# CAN_RS232.net
KiCad netlist of a schematic drawn in Altium Designer
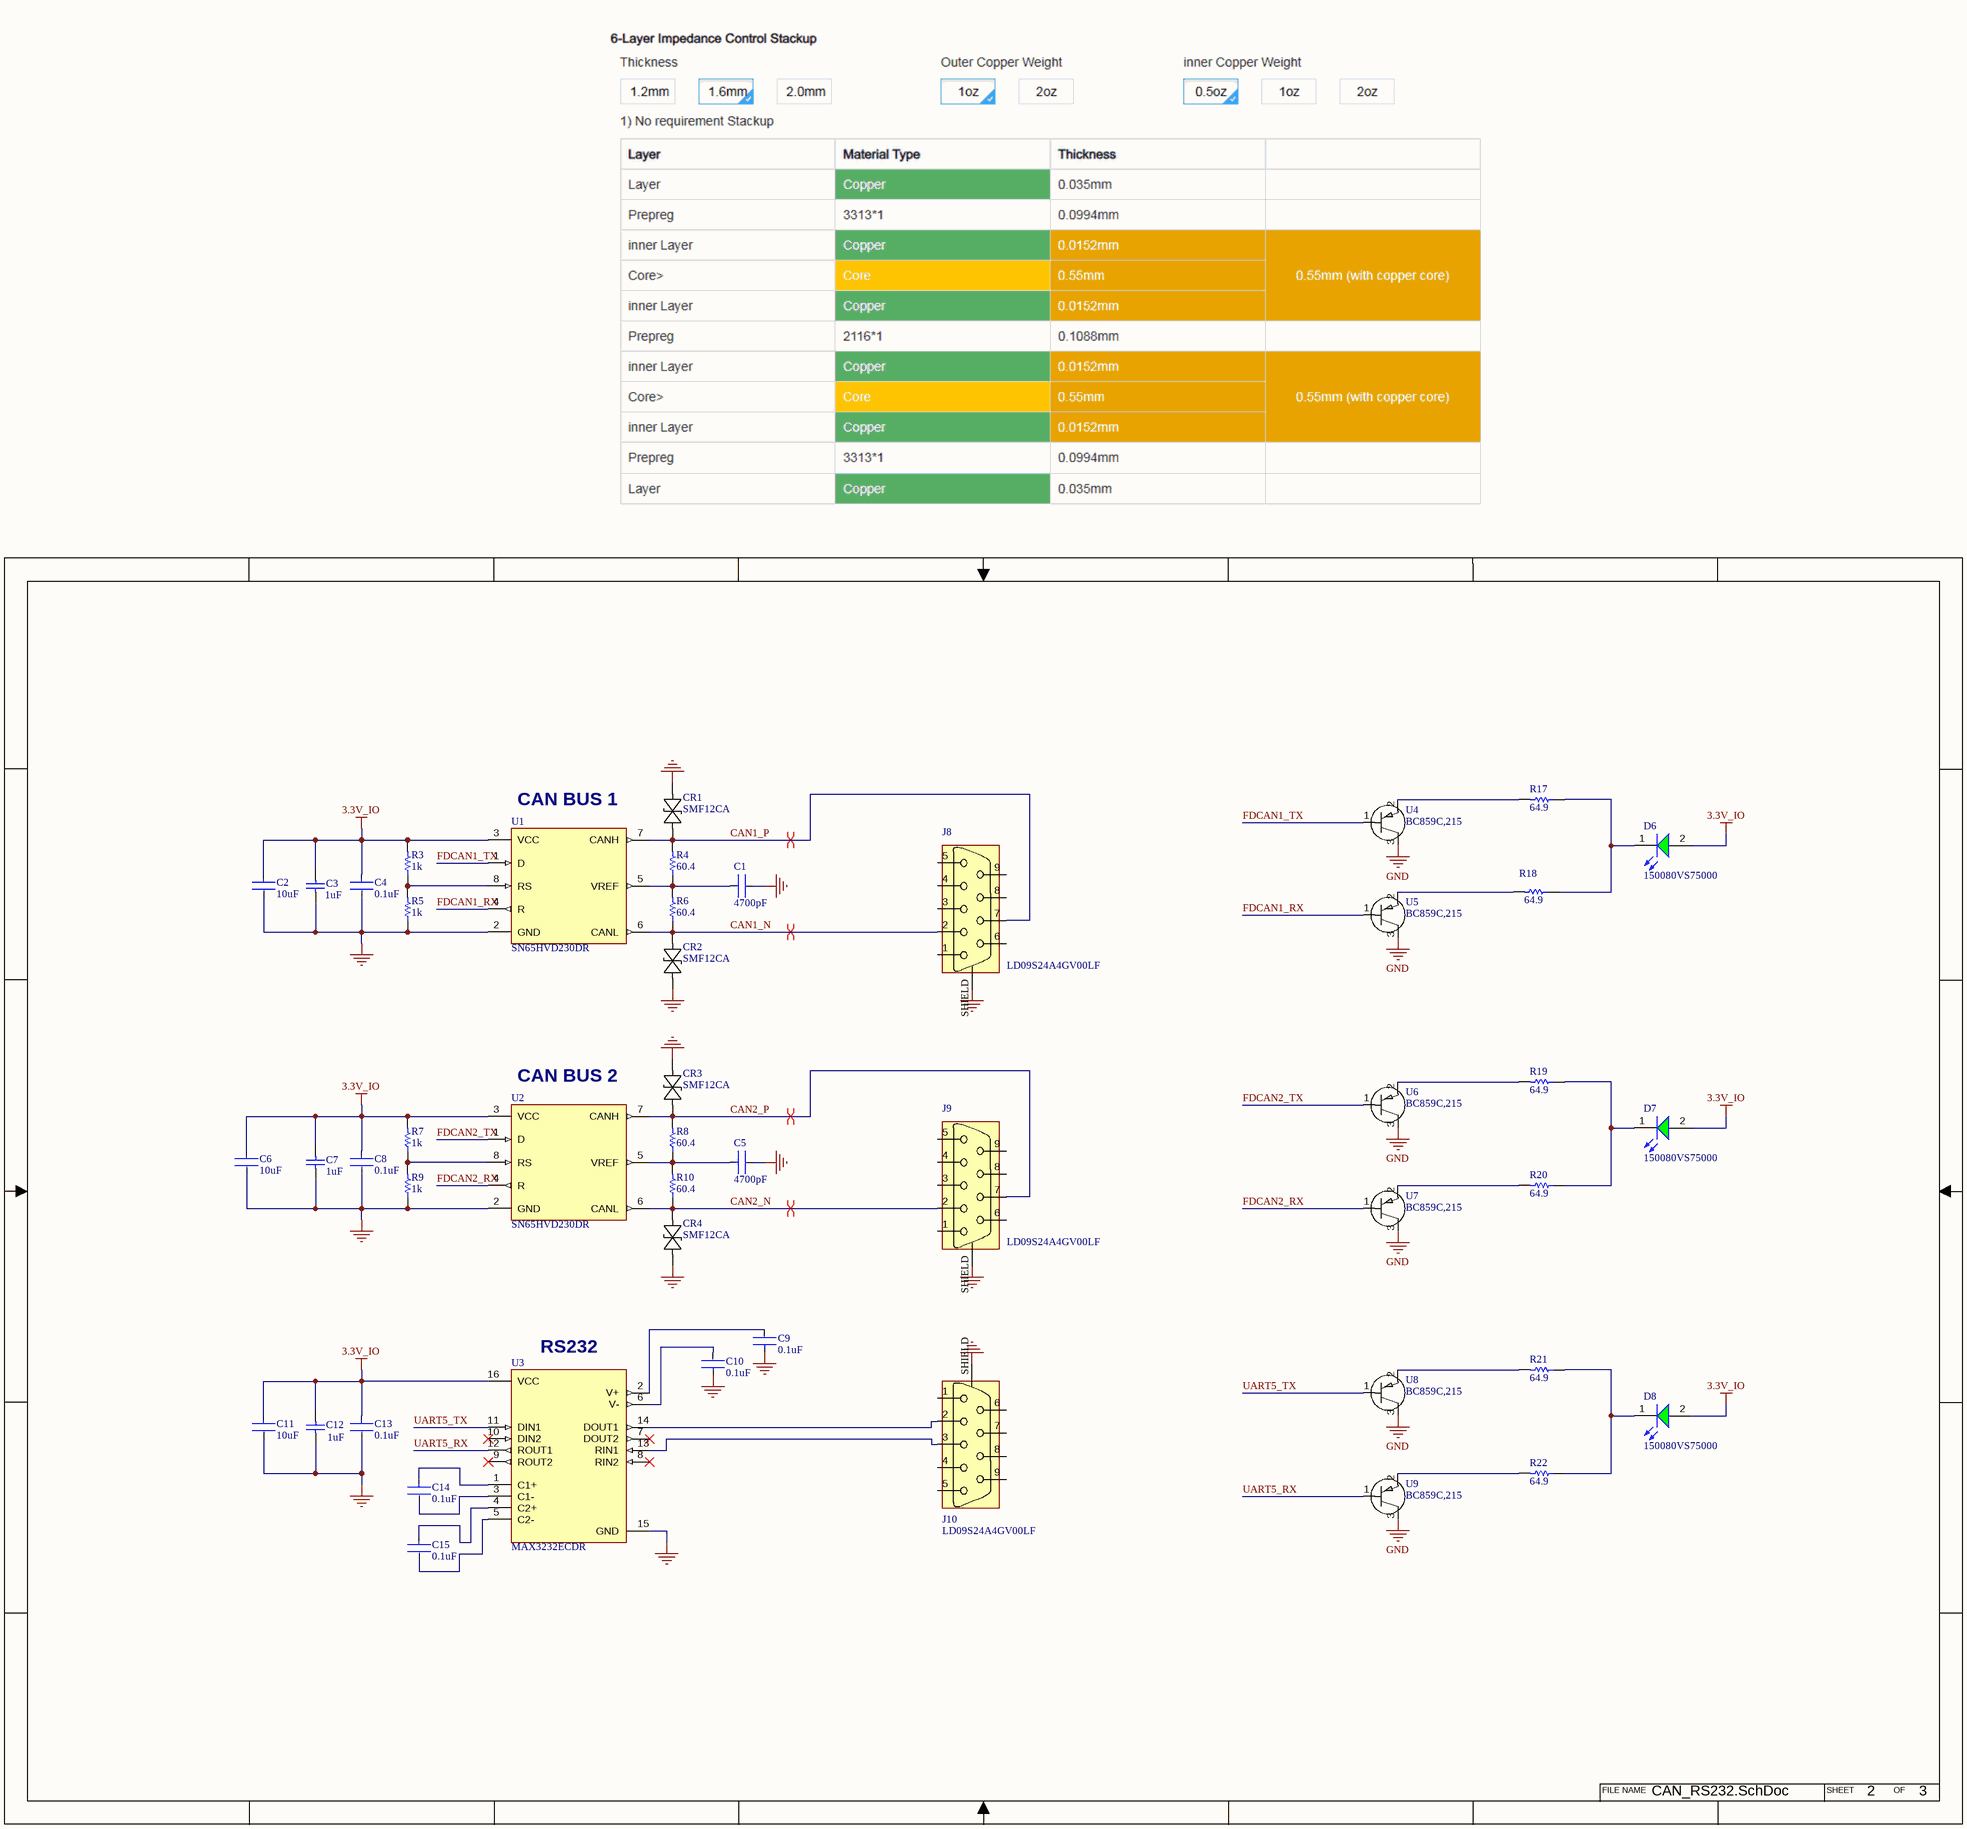
[diagram p0: CAN_RS232.SchDoc]

(export (version "E")
  (design (tool "Eeschema 10.0.6"))
  (components
    (comp (ref "C1")
      (value "4700pF")
      (footprint "FP-CC0805-0_85-MFG")
      (description "CAP CER 4700PF 50V X7R 0805")
      (fields (field (name "TOLERANCE") "0.1") (field (name "MANUFACTURER") "Yageo"))
      (libsource (lib "Altium Content Vault") (part "11868f565c42a9108669ba33697ecf6"))
    )
    (comp (ref "C2")
      (value "10uF")
      (footprint "FP-CL31-IPC_B")
      (description "Cap Ceramic 10uF 25V X7R ±10% SMD 1206 +125°C Embossed T/R")
      (fields (field (name "TOLERANCE") "10%"))
      (libsource (lib "Altium Content Vault") (part "b4654b650e69147ec39a6b967a45e02"))
    )
    (comp (ref "C3")
      (value "1uF")
      (footprint "CAPC2013X100X50ML20T25")
      (description "C0805C105K8RACTU")
      (fields (field (name "MANUFACTURER") "Kemet"))
      (libsource (lib "Altium Content Vault") (part "CAP"))
    )
    (comp (ref "C4")
      (value "0.1uF")
      (footprint "FP-CC0805-0_85-MFG")
      (description "CAP CER 0.1UF 50V X7R 0805")
      (fields (field (name "TOLERANCE") "0.1") (field (name "MANUFACTURER PART NUMBER") "CC0805KRX7R9BB104"))
      (libsource (lib "Altium Content Vault") (part "11868f565c42a9108669ba33697ecf6"))
    )
    (comp (ref "C5")
      (value "4700pF")
      (footprint "FP-CC0805-0_85-MFG")
      (description "CAP CER 4700PF 50V X7R 0805")
      (fields (field (name "TOLERANCE") "0.1") (field (name "MANUFACTURER") "Yageo"))
      (libsource (lib "Altium Content Vault") (part "11868f565c42a9108669ba33697ecf6"))
    )
    (comp (ref "C6")
      (value "10uF")
      (footprint "FP-CL31-IPC_B")
      (description "Cap Ceramic 10uF 25V X7R ±10% SMD 1206 +125°C Embossed T/R")
      (fields (field (name "TOLERANCE") "10%"))
      (libsource (lib "Altium Content Vault") (part "b4654b650e69147ec39a6b967a45e02"))
    )
    (comp (ref "C7")
      (value "1uF")
      (footprint "CAPC2013X100X50ML20T25")
      (fields (field (name "PART NUMBER") "C0805C105K8RACTU") (field (name "MANUFACTURER") "Kemet"))
      (libsource (lib "Altium Content Vault") (part "CAP"))
    )
    (comp (ref "C8")
      (value "0.1uF")
      (footprint "FP-CC0805-0_85-MFG")
      (description "CAP CER 0.1UF 50V X7R 0805")
      (fields (field (name "TOLERANCE") "0.1") (field (name "MANUFACTURER PART NUMBER") "CC0805KRX7R9BB104"))
      (libsource (lib "Altium Content Vault") (part "11868f565c42a9108669ba33697ecf6"))
    )
    (comp (ref "C9")
      (value "0.1uF")
      (footprint "FP-CC0805-0_85-MFG")
      (description "CAP CER 0.1UF 50V X7R 0805")
      (fields (field (name "TOLERANCE") "0.1") (field (name "MANUFACTURER PART NUMBER") "CC0805KRX7R9BB104"))
      (libsource (lib "Altium Content Vault") (part "11868f565c42a9108669ba33697ecf6"))
    )
    (comp (ref "C10")
      (value "0.1uF")
      (footprint "FP-CC0805-0_85-MFG")
      (description "CAP CER 0.1UF 50V X7R 0805")
      (fields (field (name "TOLERANCE") "0.1") (field (name "MANUFACTURER PART NUMBER") "CC0805KRX7R9BB104"))
      (libsource (lib "Altium Content Vault") (part "11868f565c42a9108669ba33697ecf6"))
    )
    (comp (ref "C11")
      (value "10uF")
      (footprint "FP-CL31-IPC_B")
      (description "Cap Ceramic 10uF 25V X7R ±10% SMD 1206 +125°C Embossed T/R")
      (fields (field (name "TOLERANCE") "10%"))
      (libsource (lib "Altium Content Vault") (part "b4654b650e69147ec39a6b967a45e02"))
    )
    (comp (ref "C12")
      (value "1uF")
      (footprint "CAPC2013X100X50ML20T25")
      (fields (field (name "PART NUMBER") "C0805C105K8RACTU") (field (name "MANUFACTURER") "Kemet"))
      (libsource (lib "Altium Content Vault") (part "CAP"))
    )
    (comp (ref "C13")
      (value "0.1uF")
      (footprint "FP-CC0805-0_85-MFG")
      (description "CAP CER 0.1UF 50V X7R 0805")
      (fields (field (name "TOLERANCE") "0.1") (field (name "MANUFACTURER PART NUMBER") "CC0805KRX7R9BB104"))
      (libsource (lib "Altium Content Vault") (part "11868f565c42a9108669ba33697ecf6"))
    )
    (comp (ref "C14")
      (value "0.1uF")
      (footprint "FP-CC0805-0_85-MFG")
      (description "CAP CER 0.1UF 50V X7R 0805")
      (fields (field (name "TOLERANCE") "0.1") (field (name "MANUFACTURER PART NUMBER") "CC0805KRX7R9BB104"))
      (libsource (lib "Altium Content Vault") (part "11868f565c42a9108669ba33697ecf6"))
    )
    (comp (ref "C15")
      (value "0.1uF")
      (footprint "FP-CC0805-0_85-MFG")
      (description "CAP CER 0.1UF 50V X7R 0805")
      (fields (field (name "TOLERANCE") "0.1") (field (name "MANUFACTURER PART NUMBER") "CC0805KRX7R9BB104"))
      (libsource (lib "Altium Content Vault") (part "11868f565c42a9108669ba33697ecf6"))
    )
    (comp (ref "CR1")
      (value "SMF12CA")
      (footprint "SOD-123F_LTF")
      (description "No Description Available")
      (libsource (lib "SMF12CA") (part "SMF12CA"))
    )
    (comp (ref "CR2")
      (value "SMF12CA")
      (footprint "SOD-123F_LTF")
      (description "No Description Available")
      (libsource (lib "SMF12CA") (part "SMF12CA"))
    )
    (comp (ref "CR3")
      (value "SMF12CA")
      (footprint "SOD-123F_LTF")
      (description "No Description Available")
      (libsource (lib "SMF12CA") (part "SMF12CA"))
    )
    (comp (ref "CR4")
      (value "SMF12CA")
      (footprint "SOD-123F_LTF")
      (description "No Description Available")
      (libsource (lib "SMF12CA") (part "SMF12CA"))
    )
    (comp (ref "D6")
      (value "150080VS75000")
      (footprint "WL-SMCW_0805_150080xx75000")
      (description "WL-SMCW SMT Mono-Color Chip LED Waterclear")
      (libsource (lib "Altium Content Vault") (part "LED_Green_2A-1K"))
    )
    (comp (ref "D7")
      (value "150080VS75000")
      (footprint "WL-SMCW_0805_150080xx75000")
      (description "WL-SMCW SMT Mono-Color Chip LED Waterclear")
      (libsource (lib "Altium Content Vault") (part "LED_Green_2A-1K"))
    )
    (comp (ref "D8")
      (value "150080VS75000")
      (footprint "WL-SMCW_0805_150080xx75000")
      (description "WL-SMCW SMT Mono-Color Chip LED Waterclear")
      (libsource (lib "Altium Content Vault") (part "LED_Green_2A-1K"))
    )
    (comp (ref "J8")
      (value "LD09S24A4GV00LF")
      (footprint "ASSMANN_A-DF09A/KG-T2S")
      (description "No Description Available")
      (libsource (lib "LD09S24A4GV00LF") (part "LD09S24A4GV00LF"))
    )
    (comp (ref "J9")
      (value "LD09S24A4GV00LF")
      (footprint "ASSMANN_A-DF09A/KG-T2S")
      (description "No Description Available")
      (libsource (lib "LD09S24A4GV00LF") (part "LD09S24A4GV00LF"))
    )
    (comp (ref "J10")
      (value "LD09S24A4GV00LF")
      (footprint "ASSMANN_A-DF09A/KG-T2S")
      (description "No Description Available")
      (libsource (lib "") (part "LD09S24A4GV00LF_1"))
    )
    (comp (ref "R3")
      (value "1k")
      (footprint "RESC2013X60X35ML10T20")
      (description "Chip Resistor, 1 KOhm, +/- 1%, 125 mW, -55 to 155 degC, 0805 (2012 Metric), RoHS, Tape and Reel")
      (fields (field (name "TOLERANCE") "1%") (field (name "MANUFACTURER") "Yageo"))
      (libsource (lib "Altium Content Vault") (part "RES-2"))
    )
    (comp (ref "R4")
      (value "60.4")
      (footprint "RESC2013X60X35LL10T20")
      (fields (field (name "PART NUMBER") "RC0805FR-0760R4L") (field (name "MANUFACTURER") "Yageo"))
      (libsource (lib "Altium Content Vault") (part "RES"))
    )
    (comp (ref "R5")
      (value "1k")
      (footprint "RESC2013X60X35ML10T20")
      (description "Chip Resistor, 1 KOhm, +/- 1%, 125 mW, -55 to 155 degC, 0805 (2012 Metric), RoHS, Tape and Reel")
      (fields (field (name "TOLERANCE") "1%") (field (name "MANUFACTURER") "Yageo"))
      (libsource (lib "Altium Content Vault") (part "RES-2"))
    )
    (comp (ref "R6")
      (value "60.4")
      (footprint "RESC2013X60X35LL10T20")
      (fields (field (name "PART NUMBER") "RC0805FR-0760R4L") (field (name "MANUFACTURER") "Yageo"))
      (libsource (lib "Altium Content Vault") (part "RES"))
    )
    (comp (ref "R7")
      (value "1k")
      (footprint "RESC2013X60X35ML10T20")
      (description "Chip Resistor, 1 KOhm, +/- 1%, 125 mW, -55 to 155 degC, 0805 (2012 Metric), RoHS, Tape and Reel")
      (fields (field (name "TOLERANCE") "1%") (field (name "MANUFACTURER") "Yageo"))
      (libsource (lib "Altium Content Vault") (part "RES-2"))
    )
    (comp (ref "R8")
      (value "60.4")
      (footprint "RESC2013X60X35LL10T20")
      (fields (field (name "PART NUMBER") "RC0805FR-0760R4L") (field (name "MANUFACTURER") "Yageo"))
      (libsource (lib "Altium Content Vault") (part "RES"))
    )
    (comp (ref "R9")
      (value "1k")
      (footprint "RESC2013X60X35ML10T20")
      (description "Chip Resistor, 1 KOhm, +/- 1%, 125 mW, -55 to 155 degC, 0805 (2012 Metric), RoHS, Tape and Reel")
      (fields (field (name "TOLERANCE") "1%") (field (name "MANUFACTURER") "Yageo"))
      (libsource (lib "Altium Content Vault") (part "RES-2"))
    )
    (comp (ref "R10")
      (value "60.4")
      (footprint "RESC2013X60X35LL10T20")
      (fields (field (name "PART NUMBER") "RC0805FR-0760R4L") (field (name "MANUFACTURER") "Yageo"))
      (libsource (lib "Altium Content Vault") (part "RES"))
    )
    (comp (ref "R17")
      (value "64.9")
      (footprint "RESC2013X60X35LL10T20")
      (fields (field (name "PART NUMBER") "RC0805FR-0764R9L") (field (name "MANUFACTURER") "Yageo"))
      (libsource (lib "Altium Content Vault") (part "RES"))
    )
    (comp (ref "R18")
      (value "64.9")
      (footprint "RESC2013X60X35LL10T20")
      (fields (field (name "PART NUMBER") "RC0805FR-0764R9L") (field (name "MANUFACTURER") "Yageo"))
      (libsource (lib "Altium Content Vault") (part "RES"))
    )
    (comp (ref "R19")
      (value "64.9")
      (footprint "RESC2013X60X35LL10T20")
      (fields (field (name "PART NUMBER") "RC0805FR-0764R9L") (field (name "MANUFACTURER") "Yageo"))
      (libsource (lib "Altium Content Vault") (part "RES"))
    )
    (comp (ref "R20")
      (value "64.9")
      (footprint "RESC2013X60X35LL10T20")
      (fields (field (name "PART NUMBER") "RC0805FR-0764R9L") (field (name "MANUFACTURER") "Yageo"))
      (libsource (lib "Altium Content Vault") (part "RES"))
    )
    (comp (ref "R21")
      (value "64.9")
      (footprint "RESC2013X60X35LL10T20")
      (fields (field (name "PART NUMBER") "RC0805FR-0764R9L") (field (name "MANUFACTURER") "Yageo"))
      (libsource (lib "Altium Content Vault") (part "RES"))
    )
    (comp (ref "R22")
      (value "64.9")
      (footprint "RESC2013X60X35LL10T20")
      (fields (field (name "PART NUMBER") "RC0805FR-0764R9L") (field (name "MANUFACTURER") "Yageo"))
      (libsource (lib "Altium Content Vault") (part "RES"))
    )
    (comp (ref "U1")
      (value "SN65HVD230DR")
      (footprint "SOIC127P599X175-8N")
      (description "3.3 V CAN Transceiver with Standby Mode 8-SOIC -40 to 85")
      (fields (field (name "MF") "Texas Instruments"))
      (libsource (lib "ertc_symbols") (part "SN65HVD230DR"))
    )
    (comp (ref "U2")
      (value "SN65HVD230DR")
      (footprint "SOIC127P599X175-8N")
      (description "3.3 V CAN Transceiver with Standby Mode 8-SOIC -40 to 85")
      (fields (field (name "MF") "Texas Instruments"))
      (libsource (lib "ertc_symbols") (part "SN65HVD230DR"))
    )
    (comp (ref "U3")
      (value "MAX3232ECDR")
      (footprint "SOIC127P600X175-16N:SOIC127P600X175-16N")
      (libsource (lib "MAX3232ECDR") (part "MAX3232ECDR"))
    )
    (comp (ref "U4")
      (value "BC859C,215")
      (footprint "SOT23_NEX")
      (description "No Description Available")
      (libsource (lib "BC859C,215") (part "BC859C,215"))
    )
    (comp (ref "U5")
      (value "BC859C,215")
      (footprint "SOT23_NEX")
      (description "No Description Available")
      (libsource (lib "BC859C,215") (part "BC859C,215"))
    )
    (comp (ref "U6")
      (value "BC859C,215")
      (footprint "SOT23_NEX")
      (description "No Description Available")
      (libsource (lib "BC859C,215") (part "BC859C,215"))
    )
    (comp (ref "U7")
      (value "BC859C,215")
      (footprint "SOT23_NEX")
      (description "No Description Available")
      (libsource (lib "BC859C,215") (part "BC859C,215"))
    )
    (comp (ref "U8")
      (value "BC859C,215")
      (footprint "SOT23_NEX")
      (description "No Description Available")
      (libsource (lib "BC859C,215") (part "BC859C,215"))
    )
    (comp (ref "U9")
      (value "BC859C,215")
      (footprint "SOT23_NEX")
      (description "No Description Available")
      (libsource (lib "BC859C,215") (part "BC859C,215"))
    )
  )
  (nets
    (net (code "1") (name "/CAN1_N") (class "Default")
      (node (ref "CR2") (pin "2") (pinfunction "2_2") (pintype "passive"))
      (node (ref "J8") (pin "2") (pinfunction "2_2") (pintype "passive"))
      (node (ref "R6") (pin "1") (pinfunction "1_1") (pintype "passive"))
      (node (ref "U1") (pin "6") (pinfunction "CANL_6") (pintype "output"))
    )
    (net (code "2") (name "/CAN1_P") (class "Default")
      (node (ref "CR1") (pin "2") (pinfunction "2_2") (pintype "passive"))
      (node (ref "J8") (pin "7") (pinfunction "7_7") (pintype "passive"))
      (node (ref "R4") (pin "2") (pinfunction "2_2") (pintype "passive"))
      (node (ref "U1") (pin "7") (pinfunction "CANH_7") (pintype "output"))
    )
    (net (code "3") (name "/CAN2_N") (class "Default")
      (node (ref "CR4") (pin "1") (pinfunction "1_1") (pintype "passive"))
      (node (ref "J9") (pin "2") (pinfunction "2_2") (pintype "passive"))
      (node (ref "R10") (pin "1") (pinfunction "1_1") (pintype "passive"))
      (node (ref "U2") (pin "6") (pinfunction "CANL_6") (pintype "output"))
    )
    (net (code "4") (name "/CAN2_P") (class "Default")
      (node (ref "CR3") (pin "1") (pinfunction "1_1") (pintype "passive"))
      (node (ref "J9") (pin "7") (pinfunction "7_7") (pintype "passive"))
      (node (ref "R8") (pin "2") (pinfunction "2_2") (pintype "passive"))
      (node (ref "U2") (pin "7") (pinfunction "CANH_7") (pintype "output"))
    )
    (net (code "5") (name "/FDCAN1_RX") (class "Default")
      (node (ref "U1") (pin "4") (pinfunction "R_4") (pintype "output"))
      (node (ref "U5") (pin "1") (pinfunction "Base_1") (pintype "passive"))
    )
    (net (code "6") (name "/FDCAN1_TX") (class "Default")
      (node (ref "U1") (pin "1") (pinfunction "D_1") (pintype "input"))
      (node (ref "U4") (pin "1") (pinfunction "Base_1") (pintype "passive"))
    )
    (net (code "7") (name "/FDCAN2_RX") (class "Default")
      (node (ref "U2") (pin "4") (pinfunction "R_4") (pintype "output"))
      (node (ref "U7") (pin "1") (pinfunction "Base_1") (pintype "passive"))
    )
    (net (code "8") (name "/FDCAN2_TX") (class "Default")
      (node (ref "U2") (pin "1") (pinfunction "D_1") (pintype "input"))
      (node (ref "U6") (pin "1") (pinfunction "Base_1") (pintype "passive"))
    )
    (net (code "9") (name "/UART5_RX") (class "Default")
      (node (ref "U3") (pin "12") (pinfunction "ROUT1_12") (pintype "output"))
      (node (ref "U9") (pin "1") (pinfunction "Base_1") (pintype "passive"))
    )
    (net (code "10") (name "/UART5_TX") (class "Default")
      (node (ref "U3") (pin "11") (pinfunction "DIN1_11") (pintype "input"))
      (node (ref "U8") (pin "1") (pinfunction "Base_1") (pintype "passive"))
    )
    (net (code "11") (name "3.3V_IO") (class "Default")
      (node (ref "C11") (pin "1") (pinfunction "1_1") (pintype "passive"))
      (node (ref "C12") (pin "2") (pinfunction "2_2") (pintype "passive"))
      (node (ref "C13") (pin "1") (pinfunction "1_1") (pintype "passive"))
      (node (ref "C2") (pin "1") (pinfunction "1_1") (pintype "passive"))
      (node (ref "C3") (pin "2") (pinfunction "2_2") (pintype "passive"))
      (node (ref "C4") (pin "1") (pinfunction "1_1") (pintype "passive"))
      (node (ref "C6") (pin "1") (pinfunction "1_1") (pintype "passive"))
      (node (ref "C7") (pin "2") (pinfunction "2_2") (pintype "passive"))
      (node (ref "C8") (pin "1") (pinfunction "1_1") (pintype "passive"))
      (node (ref "D6") (pin "2") (pinfunction "A_2") (pintype "passive"))
      (node (ref "D7") (pin "2") (pinfunction "A_2") (pintype "passive"))
      (node (ref "D8") (pin "2") (pinfunction "A_2") (pintype "passive"))
      (node (ref "R3") (pin "2") (pinfunction "2_2") (pintype "passive"))
      (node (ref "R7") (pin "2") (pinfunction "2_2") (pintype "passive"))
      (node (ref "U1") (pin "3") (pinfunction "VCC_3") (pintype "power_in"))
      (node (ref "U2") (pin "3") (pinfunction "VCC_3") (pintype "power_in"))
      (node (ref "U3") (pin "16") (pinfunction "VCC_16") (pintype "power_in"))
    )
    (net (code "12") (name "GND") (class "Default")
      (node (ref "C1") (pin "2") (pinfunction "2_2") (pintype "passive"))
      (node (ref "C10") (pin "1") (pinfunction "1_1") (pintype "passive"))
      (node (ref "C11") (pin "2") (pinfunction "2_2") (pintype "passive"))
      (node (ref "C12") (pin "1") (pinfunction "1_1") (pintype "passive"))
      (node (ref "C13") (pin "2") (pinfunction "2_2") (pintype "passive"))
      (node (ref "C2") (pin "2") (pinfunction "2_2") (pintype "passive"))
      (node (ref "C3") (pin "1") (pinfunction "1_1") (pintype "passive"))
      (node (ref "C4") (pin "2") (pinfunction "2_2") (pintype "passive"))
      (node (ref "C5") (pin "2") (pinfunction "2_2") (pintype "passive"))
      (node (ref "C6") (pin "2") (pinfunction "2_2") (pintype "passive"))
      (node (ref "C7") (pin "1") (pinfunction "1_1") (pintype "passive"))
      (node (ref "C8") (pin "2") (pinfunction "2_2") (pintype "passive"))
      (node (ref "C9") (pin "1") (pinfunction "1_1") (pintype "passive"))
      (node (ref "CR1") (pin "1") (pinfunction "1_1") (pintype "passive"))
      (node (ref "CR2") (pin "1") (pinfunction "1_1") (pintype "passive"))
      (node (ref "CR3") (pin "2") (pinfunction "2_2") (pintype "passive"))
      (node (ref "CR4") (pin "2") (pinfunction "2_2") (pintype "passive"))
      (node (ref "J10") (pin "SHIELD") (pinfunction "SHIELD_SHIELD") (pintype "passive"))
      (node (ref "J8") (pin "SHIELD") (pinfunction "SHIELD_SHIELD") (pintype "passive"))
      (node (ref "J9") (pin "SHIELD") (pinfunction "SHIELD_SHIELD") (pintype "passive"))
      (node (ref "R5") (pin "1") (pinfunction "1_1") (pintype "passive"))
      (node (ref "R9") (pin "1") (pinfunction "1_1") (pintype "passive"))
      (node (ref "U1") (pin "2") (pinfunction "GND_2") (pintype "power_in"))
      (node (ref "U2") (pin "2") (pinfunction "GND_2") (pintype "power_in"))
      (node (ref "U3") (pin "15") (pinfunction "GND_15") (pintype "power_in"))
      (node (ref "U4") (pin "3") (pinfunction "Collector_3") (pintype "passive"))
      (node (ref "U5") (pin "3") (pinfunction "Collector_3") (pintype "passive"))
      (node (ref "U6") (pin "3") (pinfunction "Collector_3") (pintype "passive"))
      (node (ref "U7") (pin "3") (pinfunction "Collector_3") (pintype "passive"))
      (node (ref "U8") (pin "3") (pinfunction "Collector_3") (pintype "passive"))
      (node (ref "U9") (pin "3") (pinfunction "Collector_3") (pintype "passive"))
    )
    (net (code "13") (name "Net-(D6-K)") (class "Default")
      (node (ref "D6") (pin "1") (pinfunction "K_1") (pintype "passive"))
      (node (ref "R17") (pin "1") (pinfunction "1_1") (pintype "passive"))
      (node (ref "R18") (pin "1") (pinfunction "1_1") (pintype "passive"))
    )
    (net (code "14") (name "Net-(D7-K)") (class "Default")
      (node (ref "D7") (pin "1") (pinfunction "K_1") (pintype "passive"))
      (node (ref "R19") (pin "1") (pinfunction "1_1") (pintype "passive"))
      (node (ref "R20") (pin "1") (pinfunction "1_1") (pintype "passive"))
    )
    (net (code "15") (name "Net-(D8-K)") (class "Default")
      (node (ref "D8") (pin "1") (pinfunction "K_1") (pintype "passive"))
      (node (ref "R21") (pin "1") (pinfunction "1_1") (pintype "passive"))
      (node (ref "R22") (pin "1") (pinfunction "1_1") (pintype "passive"))
    )
    (net (code "16") (name "Net-(U1-RS)") (class "Default")
      (node (ref "R3") (pin "1") (pinfunction "1_1") (pintype "passive"))
      (node (ref "R5") (pin "2") (pinfunction "2_2") (pintype "passive"))
      (node (ref "U1") (pin "8") (pinfunction "RS_8") (pintype "input"))
    )
    (net (code "17") (name "Net-(U1-VREF)") (class "Default")
      (node (ref "C1") (pin "1") (pinfunction "1_1") (pintype "passive"))
      (node (ref "R4") (pin "1") (pinfunction "1_1") (pintype "passive"))
      (node (ref "R6") (pin "2") (pinfunction "2_2") (pintype "passive"))
      (node (ref "U1") (pin "5") (pinfunction "VREF_5") (pintype "output"))
    )
    (net (code "18") (name "Net-(U2-RS)") (class "Default")
      (node (ref "R7") (pin "1") (pinfunction "1_1") (pintype "passive"))
      (node (ref "R9") (pin "2") (pinfunction "2_2") (pintype "passive"))
      (node (ref "U2") (pin "8") (pinfunction "RS_8") (pintype "input"))
    )
    (net (code "19") (name "Net-(U2-VREF)") (class "Default")
      (node (ref "C5") (pin "1") (pinfunction "1_1") (pintype "passive"))
      (node (ref "R10") (pin "2") (pinfunction "2_2") (pintype "passive"))
      (node (ref "R8") (pin "1") (pinfunction "1_1") (pintype "passive"))
      (node (ref "U2") (pin "5") (pinfunction "VREF_5") (pintype "output"))
    )
    (net (code "20") (name "Net-(U3-C1+)") (class "Default")
      (node (ref "C14") (pin "1") (pinfunction "1_1") (pintype "passive"))
      (node (ref "U3") (pin "1") (pinfunction "C1+_1") (pintype "passive"))
    )
    (net (code "21") (name "Net-(U3-C1-)") (class "Default")
      (node (ref "C14") (pin "2") (pinfunction "2_2") (pintype "passive"))
      (node (ref "U3") (pin "3") (pinfunction "C1-_3") (pintype "passive"))
    )
    (net (code "22") (name "Net-(U3-C2+)") (class "Default")
      (node (ref "C15") (pin "1") (pinfunction "1_1") (pintype "passive"))
      (node (ref "U3") (pin "4") (pinfunction "C2+_4") (pintype "passive"))
    )
    (net (code "23") (name "Net-(U3-C2-)") (class "Default")
      (node (ref "C15") (pin "2") (pinfunction "2_2") (pintype "passive"))
      (node (ref "U3") (pin "5") (pinfunction "C2-_5") (pintype "passive"))
    )
    (net (code "24") (name "Net-(U3-DOUT1)") (class "Default")
      (node (ref "J10") (pin "2") (pinfunction "2_2") (pintype "passive"))
      (node (ref "U3") (pin "14") (pinfunction "DOUT1_14") (pintype "output"))
    )
    (net (code "25") (name "Net-(U3-RIN1)") (class "Default")
      (node (ref "J10") (pin "3") (pinfunction "3_3") (pintype "passive"))
      (node (ref "U3") (pin "13") (pinfunction "RIN1_13") (pintype "input"))
    )
    (net (code "26") (name "Net-(U3-V+)") (class "Default")
      (node (ref "C9") (pin "2") (pinfunction "2_2") (pintype "passive"))
      (node (ref "U3") (pin "2") (pinfunction "V+_2") (pintype "output"))
    )
    (net (code "27") (name "Net-(U3-V-)") (class "Default")
      (node (ref "C10") (pin "2") (pinfunction "2_2") (pintype "passive"))
      (node (ref "U3") (pin "6") (pinfunction "V-_6") (pintype "output"))
    )
    (net (code "28") (name "Net-(U4-Emitter)") (class "Default")
      (node (ref "R17") (pin "2") (pinfunction "2_2") (pintype "passive"))
      (node (ref "U4") (pin "2") (pinfunction "Emitter_2") (pintype "passive"))
    )
    (net (code "29") (name "Net-(U5-Emitter)") (class "Default")
      (node (ref "R18") (pin "2") (pinfunction "2_2") (pintype "passive"))
      (node (ref "U5") (pin "2") (pinfunction "Emitter_2") (pintype "passive"))
    )
    (net (code "30") (name "Net-(U6-Emitter)") (class "Default")
      (node (ref "R19") (pin "2") (pinfunction "2_2") (pintype "passive"))
      (node (ref "U6") (pin "2") (pinfunction "Emitter_2") (pintype "passive"))
    )
    (net (code "31") (name "Net-(U7-Emitter)") (class "Default")
      (node (ref "R20") (pin "2") (pinfunction "2_2") (pintype "passive"))
      (node (ref "U7") (pin "2") (pinfunction "Emitter_2") (pintype "passive"))
    )
    (net (code "32") (name "Net-(U8-Emitter)") (class "Default")
      (node (ref "R21") (pin "2") (pinfunction "2_2") (pintype "passive"))
      (node (ref "U8") (pin "2") (pinfunction "Emitter_2") (pintype "passive"))
    )
    (net (code "33") (name "Net-(U9-Emitter)") (class "Default")
      (node (ref "R22") (pin "2") (pinfunction "2_2") (pintype "passive"))
      (node (ref "U9") (pin "2") (pinfunction "Emitter_2") (pintype "passive"))
    )
    (net (code "34") (name "unconnected-(J8-Pad1)") (class "Default")
      (node (ref "J8") (pin "1") (pinfunction "1_1") (pintype "passive"))
    )
    (net (code "35") (name "unconnected-(J8-Pad3)") (class "Default")
      (node (ref "J8") (pin "3") (pinfunction "3_3") (pintype "passive"))
    )
    (net (code "36") (name "unconnected-(J8-Pad4)") (class "Default")
      (node (ref "J8") (pin "4") (pinfunction "4_4") (pintype "passive"))
    )
    (net (code "37") (name "unconnected-(J8-Pad5)") (class "Default")
      (node (ref "J8") (pin "5") (pinfunction "5_5") (pintype "passive"))
    )
    (net (code "38") (name "unconnected-(J8-Pad6)") (class "Default")
      (node (ref "J8") (pin "6") (pinfunction "6_6") (pintype "passive"))
    )
    (net (code "39") (name "unconnected-(J8-Pad8)") (class "Default")
      (node (ref "J8") (pin "8") (pinfunction "8_8") (pintype "passive"))
    )
    (net (code "40") (name "unconnected-(J8-Pad9)") (class "Default")
      (node (ref "J8") (pin "9") (pinfunction "9_9") (pintype "passive"))
    )
    (net (code "41") (name "unconnected-(J9-Pad1)") (class "Default")
      (node (ref "J9") (pin "1") (pinfunction "1_1") (pintype "passive"))
    )
    (net (code "42") (name "unconnected-(J9-Pad3)") (class "Default")
      (node (ref "J9") (pin "3") (pinfunction "3_3") (pintype "passive"))
    )
    (net (code "43") (name "unconnected-(J9-Pad4)") (class "Default")
      (node (ref "J9") (pin "4") (pinfunction "4_4") (pintype "passive"))
    )
    (net (code "44") (name "unconnected-(J9-Pad5)") (class "Default")
      (node (ref "J9") (pin "5") (pinfunction "5_5") (pintype "passive"))
    )
    (net (code "45") (name "unconnected-(J9-Pad6)") (class "Default")
      (node (ref "J9") (pin "6") (pinfunction "6_6") (pintype "passive"))
    )
    (net (code "46") (name "unconnected-(J9-Pad8)") (class "Default")
      (node (ref "J9") (pin "8") (pinfunction "8_8") (pintype "passive"))
    )
    (net (code "47") (name "unconnected-(J9-Pad9)") (class "Default")
      (node (ref "J9") (pin "9") (pinfunction "9_9") (pintype "passive"))
    )
    (net (code "48") (name "unconnected-(J10-Pad1)") (class "Default")
      (node (ref "J10") (pin "1") (pinfunction "1_1") (pintype "passive"))
    )
    (net (code "49") (name "unconnected-(J10-Pad4)") (class "Default")
      (node (ref "J10") (pin "4") (pinfunction "4_4") (pintype "passive"))
    )
    (net (code "50") (name "unconnected-(J10-Pad5)") (class "Default")
      (node (ref "J10") (pin "5") (pinfunction "5_5") (pintype "passive"))
    )
    (net (code "51") (name "unconnected-(J10-Pad6)") (class "Default")
      (node (ref "J10") (pin "6") (pinfunction "6_6") (pintype "passive"))
    )
    (net (code "52") (name "unconnected-(J10-Pad7)") (class "Default")
      (node (ref "J10") (pin "7") (pinfunction "7_7") (pintype "passive"))
    )
    (net (code "53") (name "unconnected-(J10-Pad8)") (class "Default")
      (node (ref "J10") (pin "8") (pinfunction "8_8") (pintype "passive"))
    )
    (net (code "54") (name "unconnected-(J10-Pad9)") (class "Default")
      (node (ref "J10") (pin "9") (pinfunction "9_9") (pintype "passive"))
    )
    (net (code "55") (name "unconnected-(U3-DIN2-Pad10)") (class "Default")
      (node (ref "U3") (pin "10") (pinfunction "DIN2_10") (pintype "input+no_connect"))
    )
    (net (code "56") (name "unconnected-(U3-DOUT2-Pad7)") (class "Default")
      (node (ref "U3") (pin "7") (pinfunction "DOUT2_7") (pintype "output+no_connect"))
    )
    (net (code "57") (name "unconnected-(U3-RIN2-Pad8)") (class "Default")
      (node (ref "U3") (pin "8") (pinfunction "RIN2_8") (pintype "input+no_connect"))
    )
    (net (code "58") (name "unconnected-(U3-ROUT2-Pad9)") (class "Default")
      (node (ref "U3") (pin "9") (pinfunction "ROUT2_9") (pintype "output+no_connect"))
    )
  )
)
